# JBC_SolderingIron.net
KiCad netlist of a schematic drawn in Altium Designer
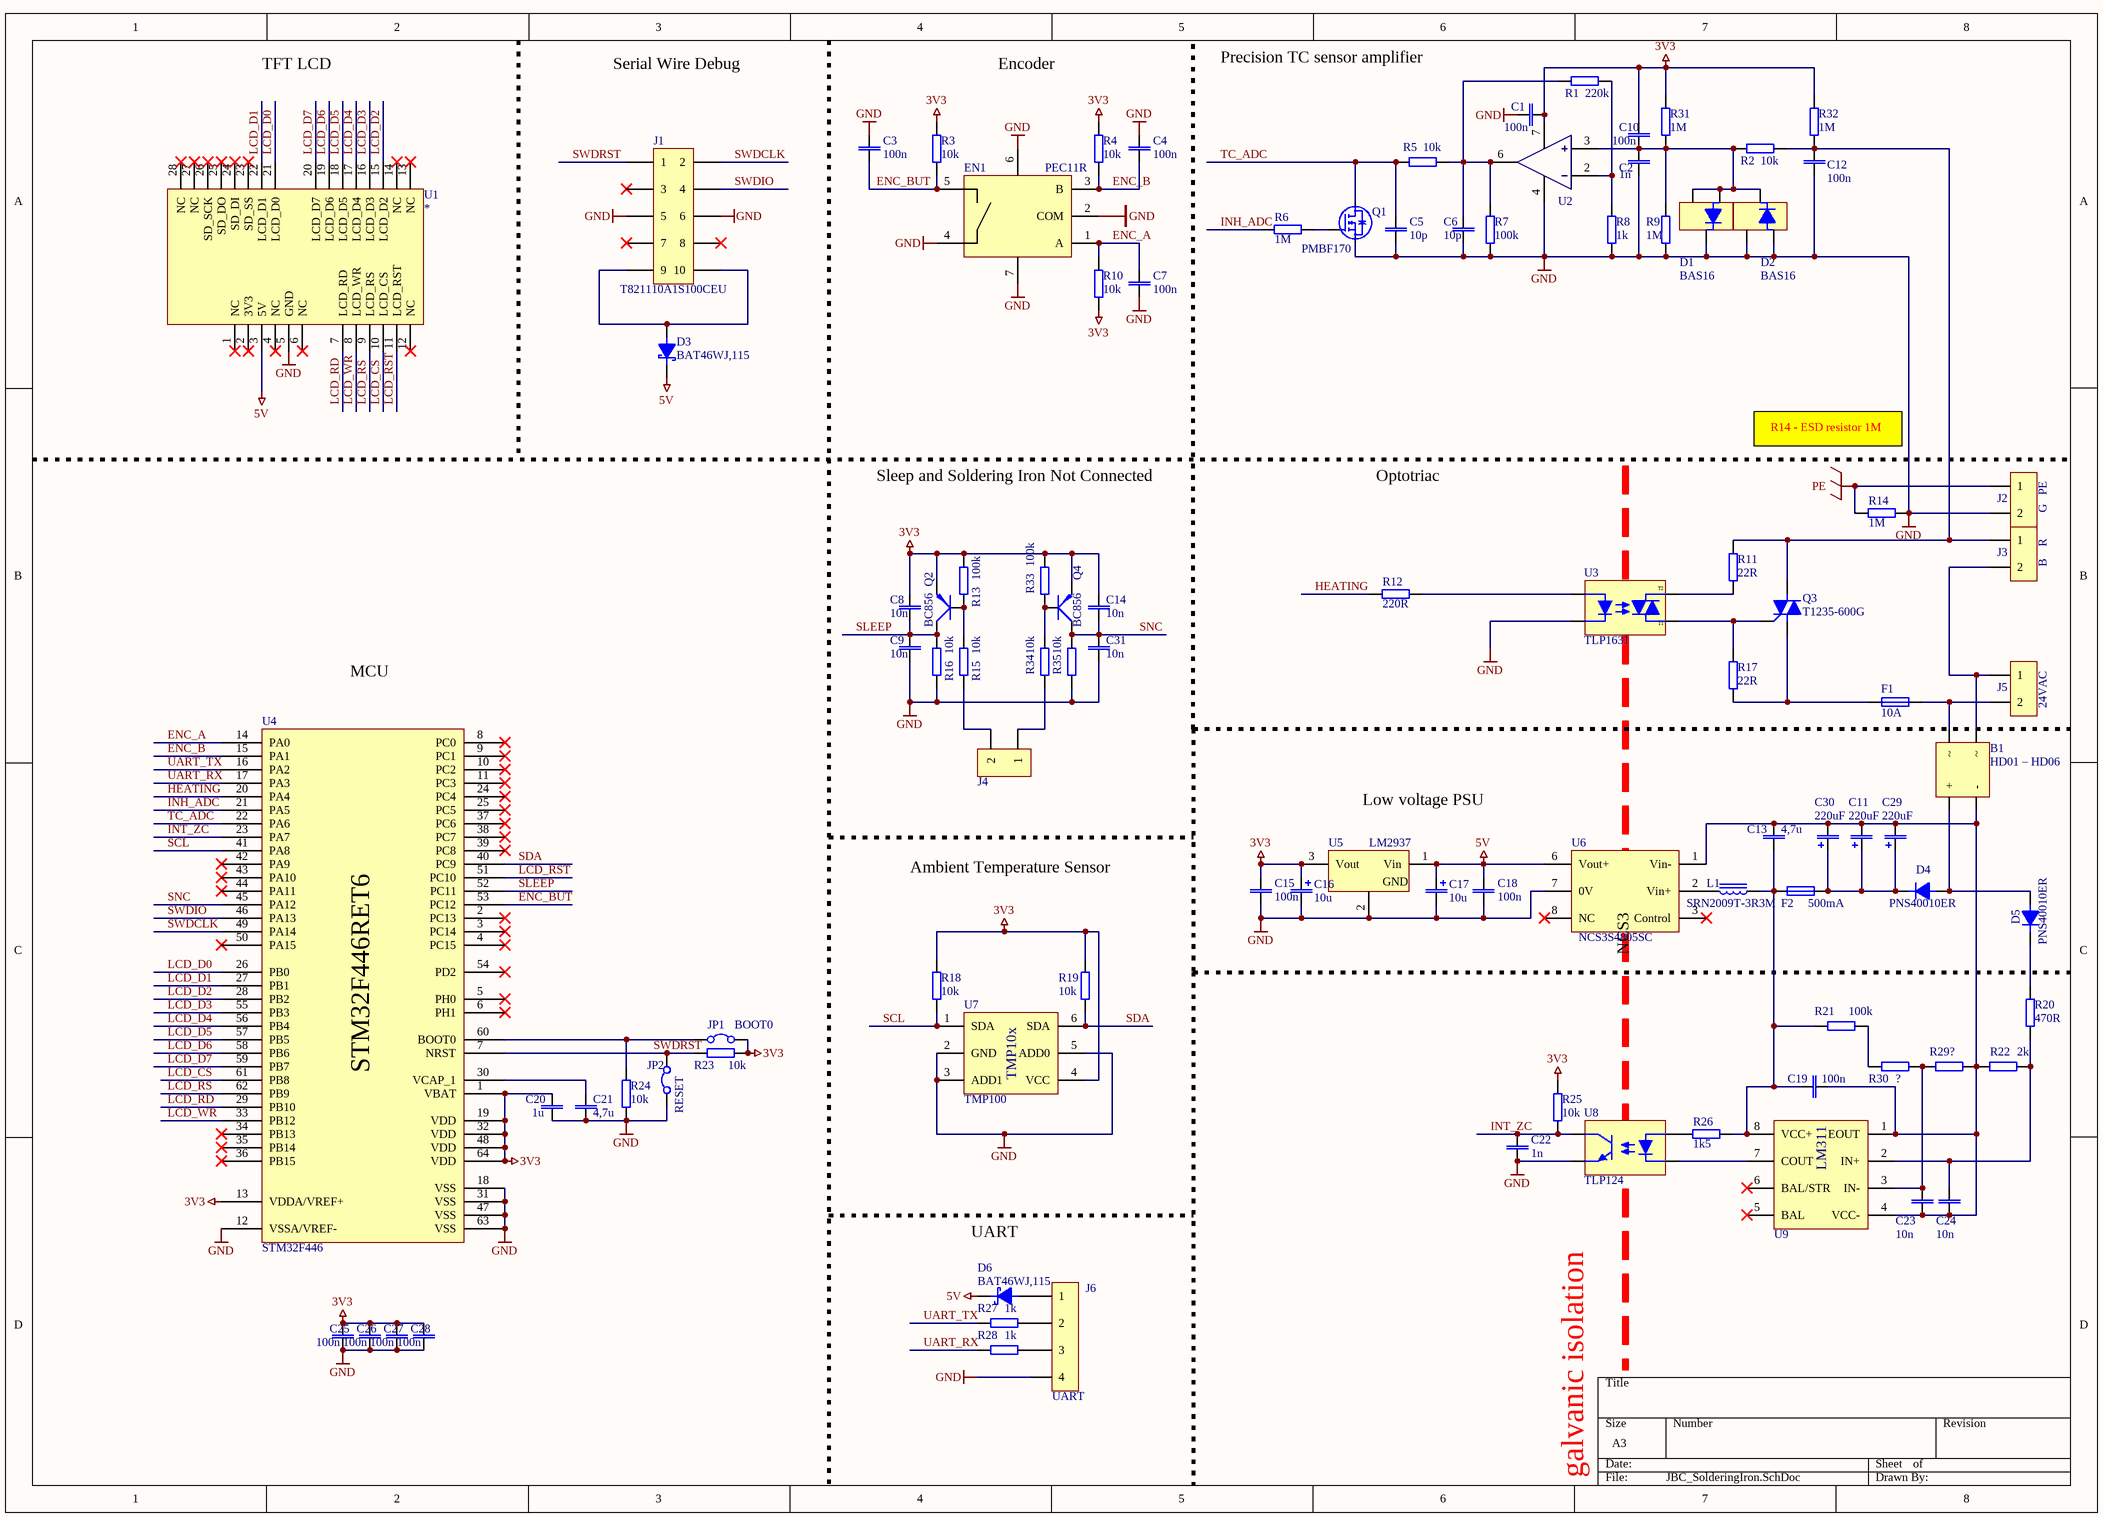
[diagram p0: JBC_SolderingIron.SchDoc]

(export (version "E")
  (design (tool "Eeschema 10.0.6"))
  (components
    (comp (ref "B1")
      (value "HD01 – HD06")
      (footprint "HD01–HD06")
      (description "0.8A SURFACE MOUNT GLASS PASSIVATED BRIDGE RECTIFIER")
      (fields (field (name "MANUFACTURER") "DiodesZetex"))
      (libsource (lib "SCH_LIB") (part "HD01–HD06"))
    )
    (comp (ref "C1")
      (value "100n")
      (footprint "CAP 0805")
      (description "NON POLARIZED CAPACITOR")
      (libsource (lib "SCH_LIB") (part "CAP"))
    )
    (comp (ref "C2")
      (value "1n")
      (footprint "CAP 0805")
      (description "NON POLARIZED CAPACITOR")
      (libsource (lib "SCH_LIB") (part "CAP"))
    )
    (comp (ref "C3")
      (value "100n")
      (footprint "CAP 0805")
      (description "NON POLARIZED CAPACITOR")
      (libsource (lib "SCH_LIB") (part "CAP"))
    )
    (comp (ref "C4")
      (value "100n")
      (footprint "CAP 0805")
      (description "NON POLARIZED CAPACITOR")
      (libsource (lib "SCH_LIB") (part "CAP"))
    )
    (comp (ref "C5")
      (value "10p")
      (footprint "CAP 0805")
      (description "NON POLARIZED CAPACITOR")
      (libsource (lib "SCH_LIB") (part "CAP"))
    )
    (comp (ref "C6")
      (value "10p")
      (footprint "CAP 0805")
      (description "NON POLARIZED CAPACITOR")
      (libsource (lib "SCH_LIB") (part "CAP"))
    )
    (comp (ref "C7")
      (value "100n")
      (footprint "CAP 0805")
      (description "NON POLARIZED CAPACITOR")
      (libsource (lib "SCH_LIB") (part "CAP"))
    )
    (comp (ref "C8")
      (value "10n")
      (footprint "CAP 0805")
      (description "NON POLARIZED CAPACITOR")
      (libsource (lib "SCH_LIB") (part "CAP"))
    )
    (comp (ref "C9")
      (value "10n")
      (footprint "CAP 0805")
      (description "NON POLARIZED CAPACITOR")
      (libsource (lib "SCH_LIB") (part "CAP"))
    )
    (comp (ref "C10")
      (value "100n")
      (footprint "CAP 0805")
      (description "NON POLARIZED CAPACITOR")
      (libsource (lib "SCH_LIB") (part "CAP"))
    )
    (comp (ref "C11")
      (value "220uF")
      (footprint "G ELKO")
      (description "POLARIZED CAPACITOR")
      (libsource (lib "SCH_LIB") (part "CAP_POL"))
    )
    (comp (ref "C12")
      (value "100n")
      (footprint "CAP 0805")
      (description "NON POLARIZED CAPACITOR")
      (libsource (lib "SCH_LIB") (part "CAP"))
    )
    (comp (ref "C13")
      (value "4,7u")
      (footprint "CAP 0805")
      (description "NON POLARIZED CAPACITOR")
      (libsource (lib "SCH_LIB") (part "CAP"))
    )
    (comp (ref "C14")
      (value "10n")
      (footprint "CAP 0805")
      (description "NON POLARIZED CAPACITOR")
      (libsource (lib "SCH_LIB") (part "CAP"))
    )
    (comp (ref "C15")
      (value "100n")
      (footprint "CAP 0805")
      (description "NON POLARIZED CAPACITOR")
      (libsource (lib "SCH_LIB") (part "CAP"))
    )
    (comp (ref "C16")
      (value "10u")
      (footprint "CAP 1210")
      (description "POLARIZED CAPACITOR")
      (libsource (lib "SCH_LIB") (part "CAP_POL"))
    )
    (comp (ref "C17")
      (value "10u")
      (footprint "CAP 1210")
      (description "POLARIZED CAPACITOR")
      (libsource (lib "SCH_LIB") (part "CAP_POL"))
    )
    (comp (ref "C18")
      (value "100n")
      (footprint "CAP 0805")
      (description "NON POLARIZED CAPACITOR")
      (libsource (lib "SCH_LIB") (part "CAP"))
    )
    (comp (ref "C19")
      (value "100n")
      (footprint "CAP 0805")
      (description "NON POLARIZED CAPACITOR")
      (libsource (lib "SCH_LIB") (part "CAP"))
    )
    (comp (ref "C20")
      (value "1u")
      (footprint "CAP 0805")
      (description "NON POLARIZED CAPACITOR")
      (libsource (lib "SCH_LIB") (part "CAP"))
    )
    (comp (ref "C21")
      (value "4,7u")
      (footprint "CAP 0805")
      (description "NON POLARIZED CAPACITOR")
      (libsource (lib "SCH_LIB") (part "CAP"))
    )
    (comp (ref "C22")
      (value "1n")
      (footprint "CAP 0805")
      (description "NON POLARIZED CAPACITOR")
      (libsource (lib "SCH_LIB") (part "CAP"))
    )
    (comp (ref "C23")
      (value "10n")
      (footprint "CAP 0805")
      (description "NON POLARIZED CAPACITOR")
      (libsource (lib "SCH_LIB") (part "CAP"))
    )
    (comp (ref "C24")
      (value "10n")
      (footprint "CAP 0805")
      (description "NON POLARIZED CAPACITOR")
      (libsource (lib "SCH_LIB") (part "CAP"))
    )
    (comp (ref "C25")
      (value "100n")
      (footprint "CAP 0805")
      (description "NON POLARIZED CAPACITOR")
      (libsource (lib "SCH_LIB") (part "CAP"))
    )
    (comp (ref "C26")
      (value "100n")
      (footprint "CAP 0805")
      (description "NON POLARIZED CAPACITOR")
      (libsource (lib "SCH_LIB") (part "CAP"))
    )
    (comp (ref "C27")
      (value "100n")
      (footprint "CAP 0805")
      (description "NON POLARIZED CAPACITOR")
      (libsource (lib "SCH_LIB") (part "CAP"))
    )
    (comp (ref "C28")
      (value "100n")
      (footprint "CAP 0805")
      (description "NON POLARIZED CAPACITOR")
      (libsource (lib "SCH_LIB") (part "CAP"))
    )
    (comp (ref "C29")
      (value "220uF")
      (footprint "G ELKO")
      (description "POLARIZED CAPACITOR")
      (libsource (lib "SCH_LIB") (part "CAP_POL"))
    )
    (comp (ref "C30")
      (value "220uF")
      (footprint "G ELKO")
      (description "POLARIZED CAPACITOR")
      (libsource (lib "SCH_LIB") (part "CAP_POL"))
    )
    (comp (ref "C31")
      (value "10n")
      (footprint "CAP 0805")
      (description "NON POLARIZED CAPACITOR")
      (libsource (lib "SCH_LIB") (part "CAP"))
    )
    (comp (ref "D1")
      (value "BAS16")
      (footprint "SOT23")
      (description "Low leakage current diode")
      (fields (field (name "MANUFACTURER") "ON Semiconductor"))
      (libsource (lib "") (part "BAS16_1"))
    )
    (comp (ref "D2")
      (value "BAS16")
      (footprint "SOT23")
      (description "Low leakage current diode")
      (fields (field (name "MANUFACTURER") "ON Semiconductor"))
      (libsource (lib "SCH_LIB") (part "BAS16"))
    )
    (comp (ref "D3")
      (value "BAT46WJ,115")
      (footprint "SOD-123")
      (description "SCHOTTKY DIODE")
      (fields (field (name "MANUFACTURER") "Nexperia"))
      (libsource (lib "SCH_LIB") (part "SCHOTTKY"))
    )
    (comp (ref "D4")
      (value "PNS40010ER")
      (footprint "SOD-123")
      (description "Nexperia PNS40010ER,115 switching diode 1.4A, 400V, SOD-123")
      (fields (field (name "MANUFACTURER") "Nexperia"))
      (libsource (lib "SCH_LIB") (part "PNS40010ER"))
    )
    (comp (ref "D5")
      (value "PNS40010ER")
      (footprint "SOD-123")
      (description "Nexperia PNS40010ER,115 switching diode 1.4A, 400V, SOD-123")
      (fields (field (name "MANUFACTURER") "Nexperia"))
      (libsource (lib "SCH_LIB") (part "PNS40010ER"))
    )
    (comp (ref "D6")
      (value "BAT46WJ,115")
      (footprint "SOD-123")
      (description "SCHOTTKY DIODE")
      (fields (field (name "MANUFACTURER") "Nexperia"))
      (libsource (lib "SCH_LIB") (part "SCHOTTKY"))
    )
    (comp (ref "EN1")
      (value "PEC11R")
      (footprint "PEC11")
      (description "Mechanical rotary encoder with pushbutton")
      (fields (field (name "MANUFACTURER") "Bourns"))
      (libsource (lib "SCH_LIB") (part "PEC11"))
    )
    (comp (ref "F1")
      (value "10A")
      (footprint "FUSE_WE5x20")
      (description "Wurth Elektronik PCB Fuse Holder, 10 (UL) A, 6.3 (VDE) A, 250V ac")
      (fields (field (name "MANUFACTURER") "Wurth Elektronik"))
      (libsource (lib "SCH_LIB") (part "FUSE_WE5x20"))
    )
    (comp (ref "F2")
      (value "500mA")
      (footprint "FUSE1812")
      (description "FUSE")
      (libsource (lib "SCH_LIB") (part "FUSE"))
    )
    (comp (ref "J1")
      (value "T821110A1S100CEU")
      (footprint "MLW10")
      (description "T821, 10pin, 2x5 connector, 2.54mm")
      (fields (field (name "MANUFACTURER") "Amphenol"))
      (libsource (lib "SCH_LIB") (part "T821-10"))
    )
    (comp (ref "J2")
      (value "G   PE")
      (footprint "PTR_AKZ350")
      (description "2 Pin Terminal Block")
      (fields (field (name "MANUFACTURER") "TE Connectivity"))
      (libsource (lib "SCH_LIB") (part "TB-2"))
    )
    (comp (ref "J3")
      (value "B    R")
      (footprint "PTR_AKZ350")
      (description "2 Pin Terminal Block")
      (fields (field (name "MANUFACTURER") "TE Connectivity"))
      (libsource (lib "SCH_LIB") (part "TB-2"))
    )
    (comp (ref "J4")
      (value "~")
      (footprint "SIL2")
      (description "2 Pin Terminal Block")
      (fields (field (name "MANUFACTURER") "TE Connectivity"))
      (libsource (lib "") (part "TB-2_1"))
    )
    (comp (ref "J5")
      (value "24VAC")
      (footprint "PTR_AKZ350")
      (description "2 Pin Terminal Block")
      (fields (field (name "MANUFACTURER") "TE Connectivity"))
      (libsource (lib "SCH_LIB") (part "TB-2"))
    )
    (comp (ref "J6")
      (value "UART")
      (footprint "SIL4")
      (description "4 PIN HEADER")
      (libsource (lib "SCH_LIB") (part "HEADER4"))
    )
    (comp (ref "JP1")
      (value "BOOT0")
      (footprint "SIL2")
      (description "JUMPER")
      (libsource (lib "SCH_LIB") (part "JUMPER"))
    )
    (comp (ref "JP2")
      (value "RESET")
      (footprint "SIL2")
      (description "JUMPER")
      (libsource (lib "SCH_LIB") (part "JUMPER"))
    )
    (comp (ref "L1")
      (value "SRN2009T-3R3M")
      (footprint "SRN2009T")
      (fields (field (name "MANUFACTURER") "Bourns"))
      (libsource (lib "SCH_LIB") (part "SRN2009T-3R3M"))
    )
    (comp (ref "Q1")
      (value "PMBF170")
      (footprint "SOT23")
      (description "N-Channel MOSFET")
      (fields (field (name "MANUFACTURER") "Nexperia"))
      (libsource (lib "SCH_LIB") (part "PMBF170"))
    )
    (comp (ref "Q2")
      (value "BC856")
      (footprint "SOT23")
      (description "PNP transistor, SOT23")
      (fields (field (name "MANUFACTURER") "ON Semiconductor"))
      (libsource (lib "SCH_LIB") (part "BC856"))
    )
    (comp (ref "Q3")
      (value "T1235-600G")
      (footprint "TO262")
      (description "ST micro T1235-600G triac")
      (fields (field (name "MANUFACTURER") "ST Microelectronics"))
      (libsource (lib "SCH_LIB") (part "T1235-600G"))
    )
    (comp (ref "Q4")
      (value "BC856")
      (footprint "SOT23")
      (description "PNP transistor, SOT23")
      (fields (field (name "MANUFACTURER") "ON Semiconductor"))
      (libsource (lib "SCH_LIB") (part "BC856"))
    )
    (comp (ref "R1")
      (value "220k")
      (footprint "RES 0805")
      (description "RESISTOR")
      (libsource (lib "") (part "RES_1"))
    )
    (comp (ref "R2")
      (value "10k")
      (footprint "RES 0805")
      (description "RESISTOR")
      (libsource (lib "") (part "RES_3"))
    )
    (comp (ref "R3")
      (value "10k")
      (footprint "RES 0805")
      (description "RESISTOR")
      (libsource (lib "SCH_LIB") (part "RES"))
    )
    (comp (ref "R4")
      (value "10k")
      (footprint "RES 0805")
      (description "RESISTOR")
      (libsource (lib "SCH_LIB") (part "RES"))
    )
    (comp (ref "R5")
      (value "10k")
      (footprint "RES 0805")
      (description "RESISTOR")
      (libsource (lib "") (part "RES_1"))
    )
    (comp (ref "R6")
      (value "1M")
      (footprint "RES 0805")
      (description "RESISTOR")
      (libsource (lib "") (part "RES_1"))
    )
    (comp (ref "R7")
      (value "100k")
      (footprint "RES 0805")
      (description "RESISTOR")
      (libsource (lib "SCH_LIB") (part "RES"))
    )
    (comp (ref "R8")
      (value "1k")
      (footprint "RES 0805")
      (description "RESISTOR")
      (libsource (lib "SCH_LIB") (part "RES"))
    )
    (comp (ref "R9")
      (value "1M")
      (footprint "RES 0805")
      (description "RESISTOR")
      (libsource (lib "SCH_LIB") (part "RES"))
    )
    (comp (ref "R10")
      (value "10k")
      (footprint "RES 0805")
      (description "RESISTOR")
      (libsource (lib "SCH_LIB") (part "RES"))
    )
    (comp (ref "R11")
      (value "22R")
      (footprint "RES 0805")
      (description "RESISTOR")
      (libsource (lib "") (part "RES_2"))
    )
    (comp (ref "R12")
      (value "220R")
      (footprint "RES 0805")
      (description "RESISTOR")
      (libsource (lib "") (part "RES_1"))
    )
    (comp (ref "R13")
      (value "100k")
      (footprint "RES 0805")
      (description "RESISTOR")
      (libsource (lib "") (part "RES_2"))
    )
    (comp (ref "R14")
      (value "1M")
      (footprint "RES 0805")
      (description "RESISTOR")
      (libsource (lib "") (part "RES_3"))
    )
    (comp (ref "R15")
      (value "10k")
      (footprint "RES 0805")
      (description "RESISTOR")
      (libsource (lib "") (part "RES_2"))
    )
    (comp (ref "R16")
      (value "10k")
      (footprint "RES 0805")
      (description "RESISTOR")
      (libsource (lib "") (part "RES_2"))
    )
    (comp (ref "R17")
      (value "22R")
      (footprint "RES 0805")
      (description "RESISTOR")
      (libsource (lib "SCH_LIB") (part "RES"))
    )
    (comp (ref "R18")
      (value "10k")
      (footprint "RES 0805")
      (description "RESISTOR")
      (libsource (lib "SCH_LIB") (part "RES"))
    )
    (comp (ref "R19")
      (value "10k")
      (footprint "RES 0805")
      (description "RESISTOR")
      (libsource (lib "SCH_LIB") (part "RES"))
    )
    (comp (ref "R20")
      (value "470R")
      (footprint "RES 0805")
      (description "RESISTOR")
      (libsource (lib "SCH_LIB") (part "RES"))
    )
    (comp (ref "R21")
      (value "100k")
      (footprint "RES 0805")
      (description "RESISTOR")
      (libsource (lib "") (part "RES_1"))
    )
    (comp (ref "R22")
      (value "2k")
      (footprint "RES 0805")
      (description "RESISTOR")
      (libsource (lib "") (part "RES_3"))
    )
    (comp (ref "R23")
      (value "10k")
      (footprint "RES 0805")
      (description "RESISTOR")
      (libsource (lib "") (part "RES_3"))
    )
    (comp (ref "R24")
      (value "10k")
      (footprint "RES 0805")
      (description "RESISTOR")
      (libsource (lib "SCH_LIB") (part "RES"))
    )
    (comp (ref "R25")
      (value "10k")
      (footprint "RES 0805")
      (description "RESISTOR")
      (libsource (lib "") (part "RES_2"))
    )
    (comp (ref "R26")
      (value "1k5")
      (footprint "RES 0805")
      (description "RESISTOR")
      (libsource (lib "") (part "RES_1"))
    )
    (comp (ref "R27")
      (value "1k")
      (footprint "RES 0805")
      (description "RESISTOR")
      (libsource (lib "") (part "RES_1"))
    )
    (comp (ref "R28")
      (value "1k")
      (footprint "RES 0805")
      (description "RESISTOR")
      (libsource (lib "") (part "RES_1"))
    )
    (comp (ref "R29")
      (value "?")
      (footprint "RES 0805")
      (description "RESISTOR")
      (libsource (lib "") (part "RES_1"))
    )
    (comp (ref "R30")
      (value "?")
      (footprint "RES 0805")
      (description "RESISTOR")
      (libsource (lib "") (part "RES_1"))
    )
    (comp (ref "R31")
      (value "1M")
      (footprint "RES 0805")
      (description "RESISTOR")
      (libsource (lib "SCH_LIB") (part "RES"))
    )
    (comp (ref "R32")
      (value "1M")
      (footprint "RES 0805")
      (description "RESISTOR")
      (libsource (lib "SCH_LIB") (part "RES"))
    )
    (comp (ref "R33")
      (value "100k")
      (footprint "RES 0805")
      (description "RESISTOR")
      (libsource (lib "") (part "RES_1"))
    )
    (comp (ref "R34")
      (value "10k")
      (footprint "RES 0805")
      (description "RESISTOR")
      (libsource (lib "") (part "RES_1"))
    )
    (comp (ref "R35")
      (value "10k")
      (footprint "RES 0805")
      (description "RESISTOR")
      (libsource (lib "") (part "RES_1"))
    )
    (comp (ref "U1")
      (value "*")
      (footprint "2.8inch_TFTLCD")
      (description "2.8 inch Adafruit LCD module")
      (libsource (lib "SCH_LIB") (part "2.8inch_TFT_LCD"))
    )
    (comp (ref "U2")
      (value "OPA335AID")
      (footprint "SO8")
      (description "Precision OPAMP, SO8")
      (fields (field (name "MANUFACTURER") "Texas Instruments"))
      (libsource (lib "SCH_LIB") (part "OPA335"))
    )
    (comp (ref "U3")
      (value "TLP163J")
      (footprint "11-4C1")
      (description "Toshiba TLP163J optotriac with zero crossing detector")
      (fields (field (name "MANUFACTURER") "Toshiba"))
      (libsource (lib "SCH_LIB") (part "TLP168J"))
    )
    (comp (ref "U4")
      (value "STM32F446")
      (footprint "LQFP64")
      (description "MCU STM32F446RET6 32bit, ARM Cortex M4, 180MHz, Flash, 128 kB RAM, 2xUSB USB, LQFP-64")
      (fields (field (name "MANUFACTURER") "ST Microelectronics"))
      (libsource (lib "SCH_LIB") (part "STM32F446RET6"))
    )
    (comp (ref "U5")
      (value "LM2937")
      (footprint "SOT223")
      (description "LDO-regulator 400mA 3,3 V 5%, 4,75 → 26 V, SOT223")
      (fields (field (name "MANUFACTURER") "Texas Instruments"))
      (libsource (lib "SCH_LIB") (part "LM2937"))
    )
    (comp (ref "U6")
      (value "NCS3S4805SC")
      (footprint "NCS3")
      (description "NCS3-SINGLE DC/DC")
      (fields (field (name "MANUFACTURER") "muRata"))
      (libsource (lib "SCH_LIB") (part "NCS3"))
    )
    (comp (ref "U7")
      (value "TMP100")
      (footprint "SOT-23-6L")
      (description "Temperature sensor with I2C interface")
      (fields (field (name "MANUFACTURER") "Texas Instruments"))
      (libsource (lib "SCH_LIB") (part "TMP10x"))
    )
    (comp (ref "U8")
      (value "TLP124")
      (footprint "11-4C1")
      (description "Transistor output optocoupler TOSHIBA TLP124")
      (fields (field (name "MANUFACTURER") "Toshiba"))
      (libsource (lib "SCH_LIB") (part "TLP124"))
    )
    (comp (ref "U9")
      (value "LM311D")
      (footprint "SO8")
      (description "LM311D -  SINGLE CHANNEL W/STROBE COMPARATOR, SO8")
      (fields (field (name "MANUFACTURER") "Texas Instruments"))
      (libsource (lib "SCH_LIB") (part "LM311"))
    )
  )
  (nets
    (net (code "1") (name "/ENC_A") (class "Default")
      (node (ref "C7") (pin "1") (pinfunction "1_1") (pintype "passive"))
      (node (ref "EN1") (pin "1") (pinfunction "A_1") (pintype "passive"))
      (node (ref "R10") (pin "2") (pinfunction "2_2") (pintype "passive"))
      (node (ref "U4") (pin "14") (pinfunction "PA0_14") (pintype "passive"))
    )
    (net (code "2") (name "/ENC_B") (class "Default")
      (node (ref "C4") (pin "2") (pinfunction "2_2") (pintype "passive"))
      (node (ref "EN1") (pin "3") (pinfunction "B_3") (pintype "passive"))
      (node (ref "R4") (pin "1") (pinfunction "1_1") (pintype "passive"))
      (node (ref "U4") (pin "15") (pinfunction "PA1_15") (pintype "passive"))
    )
    (net (code "3") (name "/ENC_BUT") (class "Default")
      (node (ref "C3") (pin "2") (pinfunction "2_2") (pintype "passive"))
      (node (ref "EN1") (pin "5") (pinfunction "5_5") (pintype "passive"))
      (node (ref "R3") (pin "1") (pinfunction "1_1") (pintype "passive"))
      (node (ref "U4") (pin "53") (pinfunction "PC12_53") (pintype "passive"))
    )
    (net (code "4") (name "/HEATING") (class "Default")
      (node (ref "R12") (pin "2") (pinfunction "2_2") (pintype "passive"))
      (node (ref "U4") (pin "20") (pinfunction "PA4_20") (pintype "passive"))
    )
    (net (code "5") (name "/INH_ADC") (class "Default")
      (node (ref "R6") (pin "2") (pinfunction "2_2") (pintype "passive"))
      (node (ref "U4") (pin "21") (pinfunction "PA5_21") (pintype "passive"))
    )
    (net (code "6") (name "/INT_ZC") (class "Default")
      (node (ref "C22") (pin "1") (pinfunction "1_1") (pintype "passive"))
      (node (ref "R25") (pin "2") (pinfunction "2_2") (pintype "passive"))
      (node (ref "U4") (pin "23") (pinfunction "PA7_23") (pintype "passive"))
      (node (ref "U8") (pin "6") (pinfunction "C_6") (pintype "passive"))
    )
    (net (code "7") (name "/LCD_CS") (class "Default")
      (node (ref "U1") (pin "10") (pinfunction "LCD_CS_10") (pintype "passive"))
      (node (ref "U4") (pin "61") (pinfunction "PB8_61") (pintype "passive"))
    )
    (net (code "8") (name "/LCD_D0") (class "Default")
      (node (ref "U1") (pin "21") (pinfunction "LCD_D0_21") (pintype "passive"))
      (node (ref "U4") (pin "26") (pinfunction "PB0_26") (pintype "passive"))
    )
    (net (code "9") (name "/LCD_D1") (class "Default")
      (node (ref "U1") (pin "22") (pinfunction "LCD_D1_22") (pintype "passive"))
      (node (ref "U4") (pin "27") (pinfunction "PB1_27") (pintype "passive"))
    )
    (net (code "10") (name "/LCD_D2") (class "Default")
      (node (ref "U1") (pin "15") (pinfunction "LCD_D2_15") (pintype "passive"))
      (node (ref "U4") (pin "28") (pinfunction "PB2_28") (pintype "passive"))
    )
    (net (code "11") (name "/LCD_D3") (class "Default")
      (node (ref "U1") (pin "16") (pinfunction "LCD_D3_16") (pintype "passive"))
      (node (ref "U4") (pin "55") (pinfunction "PB3_55") (pintype "passive"))
    )
    (net (code "12") (name "/LCD_D4") (class "Default")
      (node (ref "U1") (pin "17") (pinfunction "LCD_D4_17") (pintype "passive"))
      (node (ref "U4") (pin "56") (pinfunction "PB4_56") (pintype "passive"))
    )
    (net (code "13") (name "/LCD_D5") (class "Default")
      (node (ref "U1") (pin "18") (pinfunction "LCD_D5_18") (pintype "passive"))
      (node (ref "U4") (pin "57") (pinfunction "PB5_57") (pintype "passive"))
    )
    (net (code "14") (name "/LCD_D6") (class "Default")
      (node (ref "U1") (pin "19") (pinfunction "LCD_D6_19") (pintype "passive"))
      (node (ref "U4") (pin "58") (pinfunction "PB6_58") (pintype "passive"))
    )
    (net (code "15") (name "/LCD_D7") (class "Default")
      (node (ref "U1") (pin "20") (pinfunction "LCD_D7_20") (pintype "passive"))
      (node (ref "U4") (pin "59") (pinfunction "PB7_59") (pintype "passive"))
    )
    (net (code "16") (name "/LCD_RD") (class "Default")
      (node (ref "U1") (pin "7") (pinfunction "LCD_RD_7") (pintype "passive"))
      (node (ref "U4") (pin "29") (pinfunction "PB10_29") (pintype "passive"))
    )
    (net (code "17") (name "/LCD_RS") (class "Default")
      (node (ref "U1") (pin "9") (pinfunction "LCD_RS_9") (pintype "passive"))
      (node (ref "U4") (pin "62") (pinfunction "PB9_62") (pintype "passive"))
    )
    (net (code "18") (name "/LCD_RST") (class "Default")
      (node (ref "U1") (pin "11") (pinfunction "LCD_RST_11") (pintype "passive"))
      (node (ref "U4") (pin "51") (pinfunction "PC10_51") (pintype "passive"))
    )
    (net (code "19") (name "/LCD_WR") (class "Default")
      (node (ref "U1") (pin "8") (pinfunction "LCD_WR_8") (pintype "passive"))
      (node (ref "U4") (pin "33") (pinfunction "PB12_33") (pintype "passive"))
    )
    (net (code "20") (name "/SCL") (class "Default")
      (node (ref "R18") (pin "1") (pinfunction "1_1") (pintype "passive"))
      (node (ref "U4") (pin "41") (pinfunction "PA8_41") (pintype "passive"))
      (node (ref "U7") (pin "1") (pinfunction "SDA_1") (pintype "passive"))
    )
    (net (code "21") (name "/SDA") (class "Default")
      (node (ref "R19") (pin "1") (pinfunction "1_1") (pintype "passive"))
      (node (ref "U4") (pin "40") (pinfunction "PC9_40") (pintype "passive"))
      (node (ref "U7") (pin "6") (pinfunction "SDA_6") (pintype "passive"))
    )
    (net (code "22") (name "/SLEEP") (class "Default")
      (node (ref "C8") (pin "2") (pinfunction "2_2") (pintype "passive"))
      (node (ref "C9") (pin "1") (pinfunction "1_1") (pintype "passive"))
      (node (ref "Q2") (pin "3") (pinfunction "C_3") (pintype "passive"))
      (node (ref "R16") (pin "1") (pinfunction "1_1") (pintype "passive"))
      (node (ref "U4") (pin "52") (pinfunction "PC11_52") (pintype "passive"))
    )
    (net (code "23") (name "/SNC") (class "Default")
      (node (ref "C14") (pin "2") (pinfunction "2_2") (pintype "passive"))
      (node (ref "C31") (pin "1") (pinfunction "1_1") (pintype "passive"))
      (node (ref "Q4") (pin "3") (pinfunction "C_3") (pintype "passive"))
      (node (ref "R35") (pin "1") (pinfunction "1_1") (pintype "passive"))
      (node (ref "U4") (pin "45") (pinfunction "PA12_45") (pintype "passive"))
    )
    (net (code "24") (name "/SWDCLK") (class "Default")
      (node (ref "J1") (pin "2") (pinfunction "2_2") (pintype "passive"))
      (node (ref "U4") (pin "49") (pinfunction "PA14_49") (pintype "passive"))
    )
    (net (code "25") (name "/SWDIO") (class "Default")
      (node (ref "J1") (pin "4") (pinfunction "4_4") (pintype "passive"))
      (node (ref "U4") (pin "46") (pinfunction "PA13_46") (pintype "passive"))
    )
    (net (code "26") (name "/SWDRST") (class "Default")
      (node (ref "J1") (pin "1") (pinfunction "1_1") (pintype "passive"))
      (node (ref "JP2") (pin "2") (pinfunction "2_2") (pintype "passive"))
      (node (ref "R23") (pin "1") (pinfunction "1_1") (pintype "passive"))
      (node (ref "U4") (pin "7") (pinfunction "NRST_7") (pintype "passive"))
    )
    (net (code "27") (name "/TC_ADC") (class "Default")
      (node (ref "C5") (pin "1") (pinfunction "1_1") (pintype "passive"))
      (node (ref "Q1") (pin "3") (pinfunction "D_3") (pintype "passive"))
      (node (ref "R5") (pin "2") (pinfunction "2_2") (pintype "passive"))
      (node (ref "U4") (pin "22") (pinfunction "PA6_22") (pintype "passive"))
    )
    (net (code "28") (name "/UART_RX") (class "Default")
      (node (ref "R28") (pin "2") (pinfunction "2_2") (pintype "passive"))
      (node (ref "U4") (pin "17") (pinfunction "PA3_17") (pintype "passive"))
    )
    (net (code "29") (name "/UART_TX") (class "Default")
      (node (ref "R27") (pin "2") (pinfunction "2_2") (pintype "passive"))
      (node (ref "U4") (pin "16") (pinfunction "PA2_16") (pintype "passive"))
    )
    (net (code "30") (name "3V3") (class "Default")
      (node (ref "C1") (pin "2") (pinfunction "2_2") (pintype "passive"))
      (node (ref "C10") (pin "1") (pinfunction "1_1") (pintype "passive"))
      (node (ref "C14") (pin "1") (pinfunction "1_1") (pintype "passive"))
      (node (ref "C15") (pin "1") (pinfunction "1_1") (pintype "passive"))
      (node (ref "C16") (pin "1") (pinfunction "+_1") (pintype "passive"))
      (node (ref "C20") (pin "1") (pinfunction "1_1") (pintype "passive"))
      (node (ref "C25") (pin "2") (pinfunction "2_2") (pintype "passive"))
      (node (ref "C26") (pin "2") (pinfunction "2_2") (pintype "passive"))
      (node (ref "C27") (pin "2") (pinfunction "2_2") (pintype "passive"))
      (node (ref "C28") (pin "2") (pinfunction "2_2") (pintype "passive"))
      (node (ref "C8") (pin "1") (pinfunction "1_1") (pintype "passive"))
      (node (ref "JP1") (pin "2") (pinfunction "2_2") (pintype "passive"))
      (node (ref "Q2") (pin "2") (pinfunction "E_2") (pintype "passive"))
      (node (ref "Q4") (pin "2") (pinfunction "E_2") (pintype "passive"))
      (node (ref "R10") (pin "1") (pinfunction "1_1") (pintype "passive"))
      (node (ref "R13") (pin "1") (pinfunction "1_1") (pintype "passive"))
      (node (ref "R18") (pin "2") (pinfunction "2_2") (pintype "passive"))
      (node (ref "R19") (pin "2") (pinfunction "2_2") (pintype "passive"))
      (node (ref "R23") (pin "2") (pinfunction "2_2") (pintype "passive"))
      (node (ref "R25") (pin "1") (pinfunction "1_1") (pintype "passive"))
      (node (ref "R3") (pin "2") (pinfunction "2_2") (pintype "passive"))
      (node (ref "R31") (pin "2") (pinfunction "2_2") (pintype "passive"))
      (node (ref "R32") (pin "2") (pinfunction "2_2") (pintype "passive"))
      (node (ref "R33") (pin "1") (pinfunction "1_1") (pintype "passive"))
      (node (ref "R4") (pin "2") (pinfunction "2_2") (pintype "passive"))
      (node (ref "U2") (pin "7") (pinfunction "V+_7") (pintype "passive"))
      (node (ref "U4") (pin "1") (pinfunction "VBAT_1") (pintype "passive"))
      (node (ref "U4") (pin "13") (pinfunction "VDDA/VREF+_13") (pintype "passive"))
      (node (ref "U4") (pin "19") (pinfunction "VDD_19") (pintype "passive"))
      (node (ref "U4") (pin "32") (pinfunction "VDD_32") (pintype "passive"))
      (node (ref "U4") (pin "48") (pinfunction "VDD_48") (pintype "passive"))
      (node (ref "U4") (pin "64") (pinfunction "VDD_64") (pintype "passive"))
      (node (ref "U5") (pin "3") (pinfunction "Vout_3") (pintype "passive"))
      (node (ref "U7") (pin "4") (pinfunction "VCC_4") (pintype "passive"))
    )
    (net (code "31") (name "5V") (class "Default")
      (node (ref "C17") (pin "1") (pinfunction "+_1") (pintype "passive"))
      (node (ref "C18") (pin "1") (pinfunction "1_1") (pintype "passive"))
      (node (ref "D3") (pin "2") (pinfunction "K_2") (pintype "passive"))
      (node (ref "D6") (pin "2") (pinfunction "K_2") (pintype "passive"))
      (node (ref "U1") (pin "3") (pinfunction "5V_3") (pintype "passive"))
      (node (ref "U5") (pin "1") (pinfunction "Vin_1") (pintype "passive"))
      (node (ref "U6") (pin "6") (pinfunction "Vout+_6") (pintype "passive"))
    )
    (net (code "32") (name "GND") (class "Default")
      (node (ref "C1") (pin "1") (pinfunction "1_1") (pintype "passive"))
      (node (ref "C12") (pin "1") (pinfunction "1_1") (pintype "passive"))
      (node (ref "C15") (pin "2") (pinfunction "2_2") (pintype "passive"))
      (node (ref "C16") (pin "2") (pinfunction "-_2") (pintype "passive"))
      (node (ref "C17") (pin "2") (pinfunction "-_2") (pintype "passive"))
      (node (ref "C18") (pin "2") (pinfunction "2_2") (pintype "passive"))
      (node (ref "C2") (pin "2") (pinfunction "2_2") (pintype "passive"))
      (node (ref "C20") (pin "2") (pinfunction "2_2") (pintype "passive"))
      (node (ref "C21") (pin "1") (pinfunction "1_1") (pintype "passive"))
      (node (ref "C22") (pin "2") (pinfunction "2_2") (pintype "passive"))
      (node (ref "C25") (pin "1") (pinfunction "1_1") (pintype "passive"))
      (node (ref "C26") (pin "1") (pinfunction "1_1") (pintype "passive"))
      (node (ref "C27") (pin "1") (pinfunction "1_1") (pintype "passive"))
      (node (ref "C28") (pin "1") (pinfunction "1_1") (pintype "passive"))
      (node (ref "C3") (pin "1") (pinfunction "1_1") (pintype "passive"))
      (node (ref "C31") (pin "2") (pinfunction "2_2") (pintype "passive"))
      (node (ref "C4") (pin "1") (pinfunction "1_1") (pintype "passive"))
      (node (ref "C5") (pin "2") (pinfunction "2_2") (pintype "passive"))
      (node (ref "C6") (pin "2") (pinfunction "2_2") (pintype "passive"))
      (node (ref "C7") (pin "2") (pinfunction "2_2") (pintype "passive"))
      (node (ref "C9") (pin "2") (pinfunction "2_2") (pintype "passive"))
      (node (ref "D1") (pin "3") (pinfunction "K_3") (pintype "passive"))
      (node (ref "D2") (pin "1") (pinfunction "A_1") (pintype "passive"))
      (node (ref "D2") (pin "2") (pinfunction "NC_2") (pintype "passive"))
      (node (ref "EN1") (pin "2") (pinfunction "COM_2") (pintype "passive"))
      (node (ref "EN1") (pin "4") (pinfunction "4_4") (pintype "passive"))
      (node (ref "EN1") (pin "6") (pintype "passive"))
      (node (ref "EN1") (pin "7") (pintype "passive"))
      (node (ref "J1") (pin "5") (pinfunction "5_5") (pintype "passive"))
      (node (ref "J1") (pin "6") (pinfunction "6_6") (pintype "passive"))
      (node (ref "J2") (pin "2") (pinfunction "2_2") (pintype "passive"))
      (node (ref "J6") (pin "4") (pinfunction "4_4") (pintype "passive"))
      (node (ref "JP2") (pin "1") (pinfunction "1_1") (pintype "passive"))
      (node (ref "Q1") (pin "2") (pinfunction "S_2") (pintype "passive"))
      (node (ref "R14") (pin "2") (pinfunction "2_2") (pintype "passive"))
      (node (ref "R16") (pin "2") (pinfunction "2_2") (pintype "passive"))
      (node (ref "R24") (pin "1") (pinfunction "1_1") (pintype "passive"))
      (node (ref "R35") (pin "2") (pinfunction "2_2") (pintype "passive"))
      (node (ref "R7") (pin "1") (pinfunction "1_1") (pintype "passive"))
      (node (ref "R8") (pin "1") (pinfunction "1_1") (pintype "passive"))
      (node (ref "R9") (pin "1") (pinfunction "1_1") (pintype "passive"))
      (node (ref "U1") (pin "5") (pinfunction "GND_5") (pintype "passive"))
      (node (ref "U2") (pin "4") (pinfunction "V-_4") (pintype "passive"))
      (node (ref "U3") (pin "3") (pinfunction "K_3") (pintype "passive"))
      (node (ref "U4") (pin "12") (pinfunction "VSSA/VREF-_12") (pintype "passive"))
      (node (ref "U4") (pin "18") (pinfunction "VSS_18") (pintype "passive"))
      (node (ref "U4") (pin "31") (pinfunction "VSS_31") (pintype "passive"))
      (node (ref "U4") (pin "47") (pinfunction "VSS_47") (pintype "passive"))
      (node (ref "U4") (pin "63") (pinfunction "VSS_63") (pintype "passive"))
      (node (ref "U5") (pin "2") (pinfunction "GND_2") (pintype "passive"))
      (node (ref "U6") (pin "7") (pinfunction "0V_7") (pintype "passive"))
      (node (ref "U7") (pin "2") (pinfunction "GND_2") (pintype "passive"))
      (node (ref "U7") (pin "3") (pinfunction "ADD1_3") (pintype "passive"))
      (node (ref "U7") (pin "5") (pinfunction "ADD0_5") (pintype "passive"))
      (node (ref "U8") (pin "4") (pinfunction "E_4") (pintype "passive"))
    )
    (net (code "33") (name "Net-(B1-+)") (class "Default")
      (node (ref "B1") (pin "1") (pinfunction "+_1") (pintype "passive"))
      (node (ref "D4") (pin "1") (pinfunction "A_1") (pintype "passive"))
      (node (ref "D5") (pin "1") (pinfunction "A_1") (pintype "passive"))
    )
    (net (code "34") (name "Net-(B1--)") (class "Default")
      (node (ref "B1") (pin "2") (pinfunction "-_2") (pintype "passive"))
      (node (ref "C11") (pin "2") (pinfunction "-_2") (pintype "passive"))
      (node (ref "C13") (pin "1") (pinfunction "1_1") (pintype "passive"))
      (node (ref "C19") (pin "2") (pinfunction "2_2") (pintype "passive"))
      (node (ref "C23") (pin "2") (pinfunction "2_2") (pintype "passive"))
      (node (ref "C24") (pin "1") (pinfunction "1_1") (pintype "passive"))
      (node (ref "C29") (pin "2") (pinfunction "-_2") (pintype "passive"))
      (node (ref "C30") (pin "2") (pinfunction "-_2") (pintype "passive"))
      (node (ref "R22") (pin "1") (pinfunction "1_1") (pintype "passive"))
      (node (ref "R29") (pin "1") (pinfunction "1_1") (pintype "passive"))
      (node (ref "U6") (pin "1") (pinfunction "Vin-_1") (pintype "passive"))
      (node (ref "U9") (pin "1") (pinfunction "EOUT_1") (pintype "passive"))
      (node (ref "U9") (pin "4") (pinfunction "VCC-_4") (pintype "passive"))
    )
    (net (code "35") (name "Net-(B1-~-Pad3)") (class "Default")
      (node (ref "B1") (pin "3") (pinfunction "~_3") (pintype "passive"))
      (node (ref "J3") (pin "2") (pinfunction "2_2") (pintype "passive"))
      (node (ref "J5") (pin "1") (pinfunction "1_1") (pintype "passive"))
    )
    (net (code "36") (name "Net-(B1-~-Pad4)") (class "Default")
      (node (ref "B1") (pin "4") (pinfunction "~_4") (pintype "passive"))
      (node (ref "F1") (pin "2") (pinfunction "2_2") (pintype "passive"))
      (node (ref "J5") (pin "2") (pinfunction "2_2") (pintype "passive"))
    )
    (net (code "37") (name "Net-(C11-+)") (class "Default")
      (node (ref "C11") (pin "1") (pinfunction "+_1") (pintype "passive"))
      (node (ref "C29") (pin "1") (pinfunction "+_1") (pintype "passive"))
      (node (ref "C30") (pin "1") (pinfunction "+_1") (pintype "passive"))
      (node (ref "D4") (pin "2") (pinfunction "K_2") (pintype "passive"))
      (node (ref "F2") (pin "2") (pinfunction "2_2") (pintype "passive"))
    )
    (net (code "38") (name "Net-(D1-A)") (class "Default")
      (node (ref "C10") (pin "2") (pinfunction "2_2") (pintype "passive"))
      (node (ref "C2") (pin "1") (pinfunction "1_1") (pintype "passive"))
      (node (ref "D1") (pin "1") (pinfunction "A_1") (pintype "passive"))
      (node (ref "D1") (pin "2") (pinfunction "NC_2") (pintype "passive"))
      (node (ref "D2") (pin "3") (pinfunction "K_3") (pintype "passive"))
      (node (ref "R2") (pin "1") (pinfunction "1_1") (pintype "passive"))
      (node (ref "R31") (pin "1") (pinfunction "1_1") (pintype "passive"))
      (node (ref "R9") (pin "2") (pinfunction "2_2") (pintype "passive"))
      (node (ref "U2") (pin "3") (pinfunction "+In_3") (pintype "passive"))
    )
    (net (code "39") (name "Net-(D3-A)") (class "Default")
      (node (ref "D3") (pin "1") (pinfunction "A_1") (pintype "passive"))
      (node (ref "J1") (pin "10") (pinfunction "10_10") (pintype "passive"))
      (node (ref "J1") (pin "9") (pinfunction "9_9") (pintype "passive"))
    )
    (net (code "40") (name "Net-(D5-K)") (class "Default")
      (node (ref "D5") (pin "2") (pinfunction "K_2") (pintype "passive"))
      (node (ref "R20") (pin "2") (pinfunction "2_2") (pintype "passive"))
    )
    (net (code "41") (name "Net-(D6-A)") (class "Default")
      (node (ref "D6") (pin "1") (pinfunction "A_1") (pintype "passive"))
      (node (ref "J6") (pin "1") (pinfunction "1_1") (pintype "passive"))
    )
    (net (code "42") (name "Net-(J4-Pad1)") (class "Default")
      (node (ref "J4") (pin "1") (pinfunction "1_1") (pintype "passive"))
      (node (ref "R34") (pin "2") (pinfunction "2_2") (pintype "passive"))
    )
    (net (code "43") (name "Net-(J4-Pad2)") (class "Default")
      (node (ref "J4") (pin "2") (pinfunction "2_2") (pintype "passive"))
      (node (ref "R15") (pin "2") (pinfunction "2_2") (pintype "passive"))
    )
    (net (code "44") (name "Net-(J6-Pad2)") (class "Default")
      (node (ref "J6") (pin "2") (pinfunction "2_2") (pintype "passive"))
      (node (ref "R27") (pin "1") (pinfunction "1_1") (pintype "passive"))
    )
    (net (code "45") (name "Net-(J6-Pad3)") (class "Default")
      (node (ref "J6") (pin "3") (pinfunction "3_3") (pintype "passive"))
      (node (ref "R28") (pin "1") (pinfunction "1_1") (pintype "passive"))
    )
    (net (code "46") (name "Net-(Q1-G)") (class "Default")
      (node (ref "Q1") (pin "1") (pinfunction "G_1") (pintype "passive"))
      (node (ref "R6") (pin "1") (pinfunction "1_1") (pintype "passive"))
    )
    (net (code "47") (name "Net-(Q2-B)") (class "Default")
      (node (ref "Q2") (pin "1") (pinfunction "B_1") (pintype "passive"))
      (node (ref "R13") (pin "2") (pinfunction "2_2") (pintype "passive"))
      (node (ref "R15") (pin "1") (pinfunction "1_1") (pintype "passive"))
    )
    (net (code "48") (name "Net-(Q3-A1)") (class "Default")
      (node (ref "F1") (pin "1") (pinfunction "2_1") (pintype "passive"))
      (node (ref "Q3") (pin "1") (pinfunction "A1_1") (pintype "passive"))
      (node (ref "R17") (pin "1") (pinfunction "1_1") (pintype "passive"))
    )
    (net (code "49") (name "Net-(Q3-A2)") (class "Default")
      (node (ref "C12") (pin "2") (pinfunction "2_2") (pintype "passive"))
      (node (ref "J3") (pin "1") (pinfunction "1_1") (pintype "passive"))
      (node (ref "Q3") (pin "2") (pinfunction "A2_2") (pintype "passive"))
      (node (ref "R11") (pin "1") (pinfunction "1_1") (pintype "passive"))
      (node (ref "R2") (pin "2") (pinfunction "2_2") (pintype "passive"))
      (node (ref "R32") (pin "1") (pinfunction "1_1") (pintype "passive"))
    )
    (net (code "50") (name "Net-(Q3-G)") (class "Default")
      (node (ref "Q3") (pin "3") (pinfunction "G_3") (pintype "passive"))
      (node (ref "R17") (pin "2") (pinfunction "2_2") (pintype "passive"))
      (node (ref "U3") (pin "4") (pinfunction "T1_4") (pintype "passive"))
    )
    (net (code "51") (name "Net-(Q4-B)") (class "Default")
      (node (ref "Q4") (pin "1") (pinfunction "B_1") (pintype "passive"))
      (node (ref "R33") (pin "2") (pinfunction "2_2") (pintype "passive"))
      (node (ref "R34") (pin "1") (pinfunction "1_1") (pintype "passive"))
    )
    (net (code "52") (name "Net-(R21-Pad1)") (class "Default")
      (node (ref "R21") (pin "1") (pinfunction "1_1") (pintype "passive"))
      (node (ref "R30") (pin "2") (pinfunction "2_2") (pintype "passive"))
    )
    (net (code "53") (name "Net-(U2--In)") (class "Default")
      (node (ref "R1") (pin "1") (pinfunction "1_1") (pintype "passive"))
      (node (ref "R8") (pin "2") (pinfunction "2_2") (pintype "passive"))
      (node (ref "U2") (pin "2") (pinfunction "-In_2") (pintype "passive"))
    )
    (net (code "54") (name "Net-(U2-OUT)") (class "Default")
      (node (ref "C6") (pin "1") (pinfunction "1_1") (pintype "passive"))
      (node (ref "R1") (pin "2") (pinfunction "2_2") (pintype "passive"))
      (node (ref "R5") (pin "1") (pinfunction "1_1") (pintype "passive"))
      (node (ref "R7") (pin "2") (pinfunction "2_2") (pintype "passive"))
      (node (ref "U2") (pin "6") (pinfunction "OUT_6") (pintype "passive"))
    )
    (net (code "55") (name "Net-(U3-A)") (class "Default")
      (node (ref "R12") (pin "1") (pinfunction "1_1") (pintype "passive"))
      (node (ref "U3") (pin "1") (pinfunction "A_1") (pintype "passive"))
    )
    (net (code "56") (name "Net-(U3-T2)") (class "Default")
      (node (ref "R11") (pin "2") (pinfunction "2_2") (pintype "passive"))
      (node (ref "U3") (pin "6") (pinfunction "T2_6") (pintype "passive"))
    )
    (net (code "57") (name "Net-(U4-BOOT0)") (class "Default")
      (node (ref "JP1") (pin "1") (pinfunction "1_1") (pintype "passive"))
      (node (ref "R24") (pin "2") (pinfunction "2_2") (pintype "passive"))
      (node (ref "U4") (pin "60") (pinfunction "BOOT0_60") (pintype "passive"))
    )
    (net (code "58") (name "Net-(U4-VCAP_1)") (class "Default")
      (node (ref "C21") (pin "2") (pinfunction "2_2") (pintype "passive"))
      (node (ref "U4") (pin "30") (pinfunction "VCAP_1_30") (pintype "passive"))
    )
    (net (code "59") (name "Net-(U6-Vin+)") (class "Default")
      (node (ref "L1") (pin "2") (pinfunction "2_2") (pintype "passive"))
      (node (ref "U6") (pin "2") (pinfunction "Vin+_2") (pintype "passive"))
    )
    (net (code "60") (name "Net-(U8-A)") (class "Default")
      (node (ref "R26") (pin "2") (pinfunction "2_2") (pintype "passive"))
      (node (ref "U8") (pin "1") (pinfunction "A_1") (pintype "passive"))
    )
    (net (code "61") (name "Net-(U8-K)") (class "Default")
      (node (ref "U8") (pin "3") (pinfunction "K_3") (pintype "passive"))
      (node (ref "U9") (pin "7") (pinfunction "COUT_7") (pintype "passive"))
    )
    (net (code "62") (name "Net-(U9-IN+)") (class "Default")
      (node (ref "C24") (pin "2") (pinfunction "2_2") (pintype "passive"))
      (node (ref "R20") (pin "1") (pinfunction "1_1") (pintype "passive"))
      (node (ref "R22") (pin "2") (pinfunction "2_2") (pintype "passive"))
      (node (ref "U9") (pin "2") (pinfunction "IN+_2") (pintype "passive"))
    )
    (net (code "63") (name "Net-(U9-IN-)") (class "Default")
      (node (ref "C23") (pin "1") (pinfunction "1_1") (pintype "passive"))
      (node (ref "R29") (pin "2") (pinfunction "2_2") (pintype "passive"))
      (node (ref "R30") (pin "1") (pinfunction "1_1") (pintype "passive"))
      (node (ref "U9") (pin "3") (pinfunction "IN-_3") (pintype "passive"))
    )
    (net (code "64") (name "Net-(U9-VCC+)") (class "Default")
      (node (ref "C13") (pin "2") (pinfunction "2_2") (pintype "passive"))
      (node (ref "C19") (pin "1") (pinfunction "1_1") (pintype "passive"))
      (node (ref "F2") (pin "1") (pinfunction "2_1") (pintype "passive"))
      (node (ref "L1") (pin "1") (pinfunction "1_1") (pintype "passive"))
      (node (ref "R21") (pin "2") (pinfunction "2_2") (pintype "passive"))
      (node (ref "R26") (pin "1") (pinfunction "1_1") (pintype "passive"))
      (node (ref "U9") (pin "8") (pinfunction "VCC+_8") (pintype "passive"))
    )
    (net (code "65") (name "PE") (class "Default")
      (node (ref "J2") (pin "1") (pinfunction "1_1") (pintype "passive"))
      (node (ref "R14") (pin "1") (pinfunction "1_1") (pintype "passive"))
    )
    (net (code "66") (name "unconnected-(J1-Pad3)") (class "Default")
      (node (ref "J1") (pin "3") (pinfunction "3_3") (pintype "passive+no_connect"))
    )
    (net (code "67") (name "unconnected-(J1-Pad7)") (class "Default")
      (node (ref "J1") (pin "7") (pinfunction "7_7") (pintype "passive+no_connect"))
    )
    (net (code "68") (name "unconnected-(J1-Pad8)") (class "Default")
      (node (ref "J1") (pin "8") (pinfunction "8_8") (pintype "passive+no_connect"))
    )
    (net (code "69") (name "unconnected-(U1-3V3-Pad2)") (class "Default")
      (node (ref "U1") (pin "2") (pinfunction "3V3_2") (pintype "passive+no_connect"))
    )
    (net (code "70") (name "unconnected-(U1-NC-Pad1)") (class "Default")
      (node (ref "U1") (pin "1") (pinfunction "NC_1") (pintype "passive+no_connect"))
    )
    (net (code "71") (name "unconnected-(U1-NC-Pad4)") (class "Default")
      (node (ref "U1") (pin "4") (pinfunction "NC_4") (pintype "passive+no_connect"))
    )
    (net (code "72") (name "unconnected-(U1-NC-Pad6)") (class "Default")
      (node (ref "U1") (pin "6") (pinfunction "NC_6") (pintype "passive+no_connect"))
    )
    (net (code "73") (name "unconnected-(U1-NC-Pad12)") (class "Default")
      (node (ref "U1") (pin "12") (pinfunction "NC_12") (pintype "passive+no_connect"))
    )
    (net (code "74") (name "unconnected-(U1-NC-Pad13)") (class "Default")
      (node (ref "U1") (pin "13") (pinfunction "NC_13") (pintype "passive+no_connect"))
    )
    (net (code "75") (name "unconnected-(U1-NC-Pad14)") (class "Default")
      (node (ref "U1") (pin "14") (pinfunction "NC_14") (pintype "passive+no_connect"))
    )
    (net (code "76") (name "unconnected-(U1-NC-Pad27)") (class "Default")
      (node (ref "U1") (pin "27") (pinfunction "NC_27") (pintype "passive+no_connect"))
    )
    (net (code "77") (name "unconnected-(U1-NC-Pad28)") (class "Default")
      (node (ref "U1") (pin "28") (pinfunction "NC_28") (pintype "passive+no_connect"))
    )
    (net (code "78") (name "unconnected-(U1-SD_DI-Pad24)") (class "Default")
      (node (ref "U1") (pin "24") (pinfunction "SD_DI_24") (pintype "passive+no_connect"))
    )
    (net (code "79") (name "unconnected-(U1-SD_DO-Pad25)") (class "Default")
      (node (ref "U1") (pin "25") (pinfunction "SD_DO_25") (pintype "passive+no_connect"))
    )
    (net (code "80") (name "unconnected-(U1-SD_SCK-Pad26)") (class "Default")
      (node (ref "U1") (pin "26") (pinfunction "SD_SCK_26") (pintype "passive+no_connect"))
    )
    (net (code "81") (name "unconnected-(U1-SD_SS-Pad23)") (class "Default")
      (node (ref "U1") (pin "23") (pinfunction "SD_SS_23") (pintype "passive+no_connect"))
    )
    (net (code "82") (name "unconnected-(U4-PA9-Pad42)") (class "Default")
      (node (ref "U4") (pin "42") (pinfunction "PA9_42") (pintype "passive+no_connect"))
    )
    (net (code "83") (name "unconnected-(U4-PA10-Pad43)") (class "Default")
      (node (ref "U4") (pin "43") (pinfunction "PA10_43") (pintype "passive+no_connect"))
    )
    (net (code "84") (name "unconnected-(U4-PA11-Pad44)") (class "Default")
      (node (ref "U4") (pin "44") (pinfunction "PA11_44") (pintype "passive+no_connect"))
    )
    (net (code "85") (name "unconnected-(U4-PA15-Pad50)") (class "Default")
      (node (ref "U4") (pin "50") (pinfunction "PA15_50") (pintype "passive+no_connect"))
    )
    (net (code "86") (name "unconnected-(U4-PB13-Pad34)") (class "Default")
      (node (ref "U4") (pin "34") (pinfunction "PB13_34") (pintype "passive+no_connect"))
    )
    (net (code "87") (name "unconnected-(U4-PB14-Pad35)") (class "Default")
      (node (ref "U4") (pin "35") (pinfunction "PB14_35") (pintype "passive+no_connect"))
    )
    (net (code "88") (name "unconnected-(U4-PB15-Pad36)") (class "Default")
      (node (ref "U4") (pin "36") (pinfunction "PB15_36") (pintype "passive+no_connect"))
    )
    (net (code "89") (name "unconnected-(U4-PC0-Pad8)") (class "Default")
      (node (ref "U4") (pin "8") (pinfunction "PC0_8") (pintype "passive+no_connect"))
    )
    (net (code "90") (name "unconnected-(U4-PC1-Pad9)") (class "Default")
      (node (ref "U4") (pin "9") (pinfunction "PC1_9") (pintype "passive+no_connect"))
    )
    (net (code "91") (name "unconnected-(U4-PC2-Pad10)") (class "Default")
      (node (ref "U4") (pin "10") (pinfunction "PC2_10") (pintype "passive+no_connect"))
    )
    (net (code "92") (name "unconnected-(U4-PC3-Pad11)") (class "Default")
      (node (ref "U4") (pin "11") (pinfunction "PC3_11") (pintype "passive+no_connect"))
    )
    (net (code "93") (name "unconnected-(U4-PC4-Pad24)") (class "Default")
      (node (ref "U4") (pin "24") (pinfunction "PC4_24") (pintype "passive+no_connect"))
    )
    (net (code "94") (name "unconnected-(U4-PC5-Pad25)") (class "Default")
      (node (ref "U4") (pin "25") (pinfunction "PC5_25") (pintype "passive+no_connect"))
    )
    (net (code "95") (name "unconnected-(U4-PC6-Pad37)") (class "Default")
      (node (ref "U4") (pin "37") (pinfunction "PC6_37") (pintype "passive+no_connect"))
    )
    (net (code "96") (name "unconnected-(U4-PC7-Pad38)") (class "Default")
      (node (ref "U4") (pin "38") (pinfunction "PC7_38") (pintype "passive+no_connect"))
    )
    (net (code "97") (name "unconnected-(U4-PC8-Pad39)") (class "Default")
      (node (ref "U4") (pin "39") (pinfunction "PC8_39") (pintype "passive+no_connect"))
    )
    (net (code "98") (name "unconnected-(U4-PC13-Pad2)") (class "Default")
      (node (ref "U4") (pin "2") (pinfunction "PC13_2") (pintype "passive+no_connect"))
    )
    (net (code "99") (name "unconnected-(U4-PC14-Pad3)") (class "Default")
      (node (ref "U4") (pin "3") (pinfunction "PC14_3") (pintype "passive+no_connect"))
    )
    (net (code "100") (name "unconnected-(U4-PC15-Pad4)") (class "Default")
      (node (ref "U4") (pin "4") (pinfunction "PC15_4") (pintype "passive+no_connect"))
    )
    (net (code "101") (name "unconnected-(U4-PD2-Pad54)") (class "Default")
      (node (ref "U4") (pin "54") (pinfunction "PD2_54") (pintype "passive+no_connect"))
    )
    (net (code "102") (name "unconnected-(U4-PH0-Pad5)") (class "Default")
      (node (ref "U4") (pin "5") (pinfunction "PH0_5") (pintype "passive+no_connect"))
    )
    (net (code "103") (name "unconnected-(U4-PH1-Pad6)") (class "Default")
      (node (ref "U4") (pin "6") (pinfunction "PH1_6") (pintype "passive+no_connect"))
    )
    (net (code "104") (name "unconnected-(U6-Control-Pad3)") (class "Default")
      (node (ref "U6") (pin "3") (pinfunction "Control_3") (pintype "passive+no_connect"))
    )
    (net (code "105") (name "unconnected-(U6-NC-Pad8)") (class "Default")
      (node (ref "U6") (pin "8") (pinfunction "NC_8") (pintype "passive+no_connect"))
    )
    (net (code "106") (name "unconnected-(U9-BAL-Pad5)") (class "Default")
      (node (ref "U9") (pin "5") (pinfunction "BAL_5") (pintype "passive+no_connect"))
    )
    (net (code "107") (name "unconnected-(U9-BAL{slash}STR-Pad6)") (class "Default")
      (node (ref "U9") (pin "6") (pinfunction "BAL/STR_6") (pintype "passive+no_connect"))
    )
  )
)
